# main1.net
KiCad netlist of a schematic drawn in EAGLE
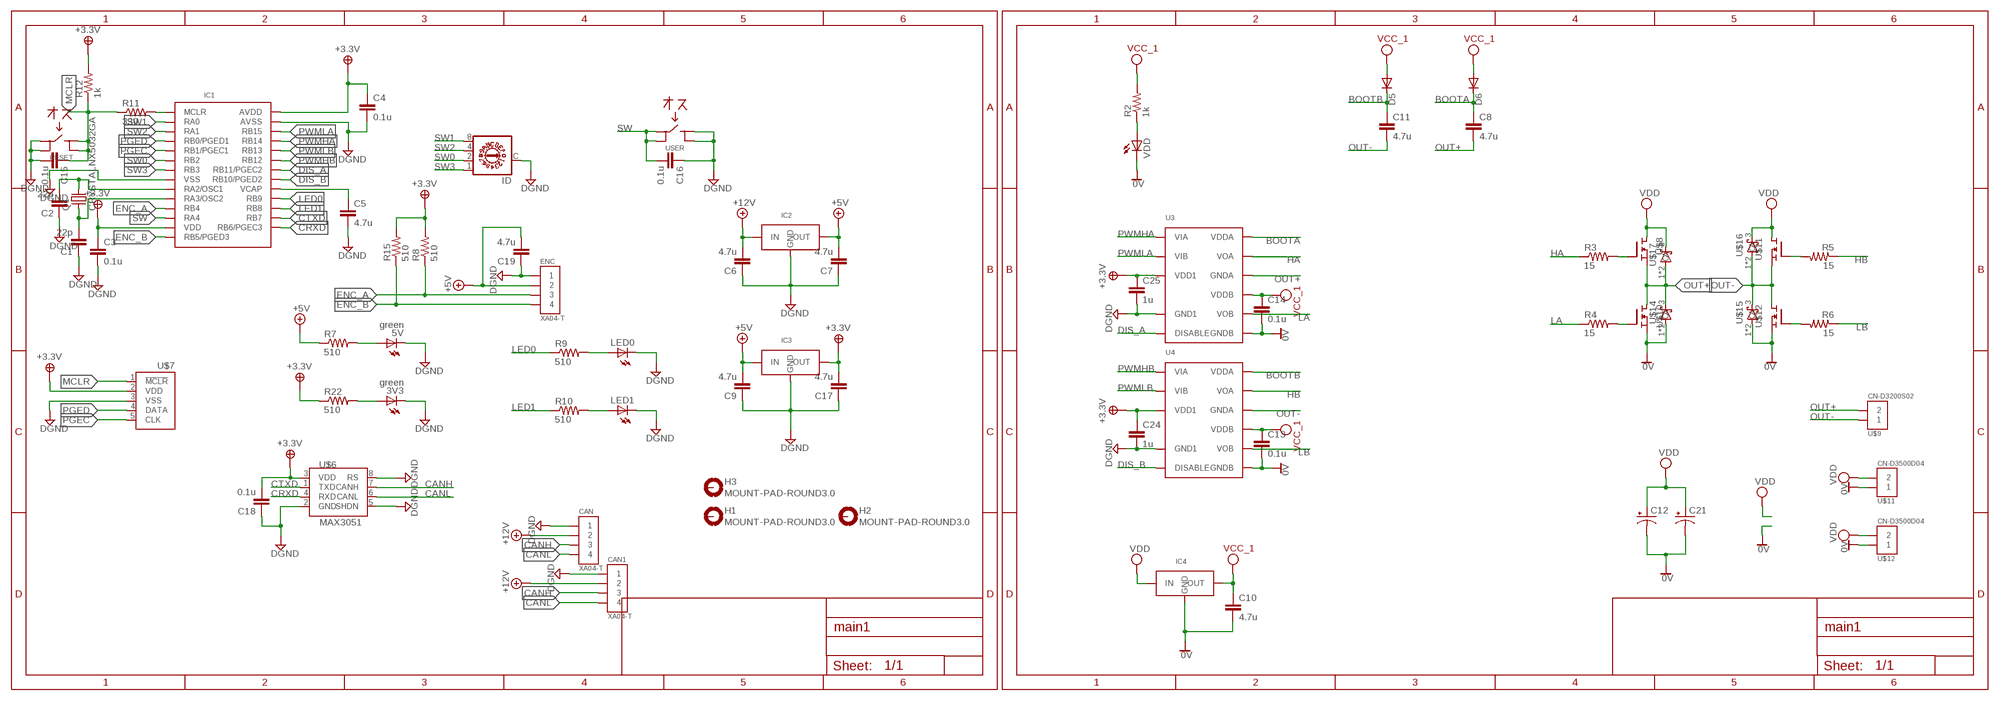
[diagram p0: schematic, sheet 1]

(export (version "E")
  (design (tool "Eeschema 10.0.6"))
  (components
    (comp (ref "3V3")
      (value "green")
      (footprint "eagle-import:CHIPLED_0603")
      (libsource (lib "eagle-import") (part "LEDCHIPLED_0603"))
    )
    (comp (ref "5V")
      (value "green")
      (footprint "eagle-import:CHIPLED_0603")
      (libsource (lib "eagle-import") (part "LEDCHIPLED_0603"))
    )
    (comp (ref "C1")
      (value "22p")
      (footprint "eagle-import:C0603K")
      (libsource (lib "eagle-import") (part "C-EUC0603K"))
    )
    (comp (ref "C2")
      (value "22p")
      (footprint "eagle-import:C0603K")
      (libsource (lib "eagle-import") (part "C-EUC0603K"))
    )
    (comp (ref "C3")
      (value "0.1u")
      (footprint "eagle-import:C0603K")
      (libsource (lib "eagle-import") (part "C-EUC0603K"))
    )
    (comp (ref "C4")
      (value "0.1u")
      (footprint "eagle-import:C0603K")
      (libsource (lib "eagle-import") (part "C-EUC0603K"))
    )
    (comp (ref "C5")
      (value "4.7u")
      (footprint "eagle-import:C0805K")
      (libsource (lib "eagle-import") (part "C-EUC0805K"))
    )
    (comp (ref "C6")
      (value "4.7u")
      (footprint "eagle-import:C0805K")
      (libsource (lib "eagle-import") (part "C-EUC0805K"))
    )
    (comp (ref "C7")
      (value "4.7u")
      (footprint "eagle-import:C0805K")
      (libsource (lib "eagle-import") (part "C-EUC0805K"))
    )
    (comp (ref "C8")
      (value "4.7u")
      (footprint "eagle-import:C0805K")
      (libsource (lib "eagle-import") (part "C-EUC0805K"))
    )
    (comp (ref "C9")
      (value "4.7u")
      (footprint "eagle-import:C0805K")
      (libsource (lib "eagle-import") (part "C-EUC0805K"))
    )
    (comp (ref "C10")
      (value "4.7u")
      (footprint "eagle-import:C0805K")
      (libsource (lib "eagle-import") (part "C-EUC0805K"))
    )
    (comp (ref "C11")
      (value "4.7u")
      (footprint "eagle-import:C0805K")
      (libsource (lib "eagle-import") (part "C-EUC0805K"))
    )
    (comp (ref "C12")
      (value "CPOL-USG")
      (footprint "eagle-import:PANASONIC_G")
      (libsource (lib "eagle-import") (part "CPOL-USG"))
    )
    (comp (ref "C13")
      (value "0.1u")
      (footprint "eagle-import:C0805K")
      (libsource (lib "eagle-import") (part "C-EUC0805K"))
    )
    (comp (ref "C14")
      (value "0.1u")
      (footprint "eagle-import:C0805K")
      (libsource (lib "eagle-import") (part "C-EUC0805K"))
    )
    (comp (ref "C15")
      (value "0.1u")
      (footprint "eagle-import:C0603K")
      (libsource (lib "eagle-import") (part "C-EUC0603K"))
    )
    (comp (ref "C16")
      (value "0.1u")
      (footprint "eagle-import:C0603K")
      (libsource (lib "eagle-import") (part "C-EUC0603K"))
    )
    (comp (ref "C17")
      (value "4.7u")
      (footprint "eagle-import:C0805K")
      (libsource (lib "eagle-import") (part "C-EUC0805K"))
    )
    (comp (ref "C18")
      (value "0.1u")
      (footprint "eagle-import:C0603K")
      (libsource (lib "eagle-import") (part "C-EUC0603K"))
    )
    (comp (ref "C19")
      (value "4.7u")
      (footprint "eagle-import:C0805K")
      (libsource (lib "eagle-import") (part "C-EUC0805K"))
    )
    (comp (ref "C21")
      (value "CPOL-USG")
      (footprint "eagle-import:PANASONIC_G")
      (libsource (lib "eagle-import") (part "CPOL-USG"))
    )
    (comp (ref "C24")
      (value "1u")
      (footprint "eagle-import:C0603K")
      (libsource (lib "eagle-import") (part "C-EUC0603K"))
    )
    (comp (ref "C25")
      (value "1u")
      (footprint "eagle-import:C0603K")
      (libsource (lib "eagle-import") (part "C-EUC0603K"))
    )
    (comp (ref "CAN")
      (value "XA04-T")
      (footprint "eagle-import:XA04")
      (libsource (lib "eagle-import") (part "XA04-T"))
    )
    (comp (ref "CAN1")
      (value "XA04-T")
      (footprint "eagle-import:XA04")
      (libsource (lib "eagle-import") (part "XA04-T"))
    )
    (comp (ref "D5")
      (value "DIODE-SOD123")
      (footprint "eagle-import:SOD123")
      (libsource (lib "eagle-import") (part "DIODE-SOD123"))
    )
    (comp (ref "D6")
      (value "DIODE-SOD123")
      (footprint "eagle-import:SOD123")
      (libsource (lib "eagle-import") (part "DIODE-SOD123"))
    )
    (comp (ref "ENC")
      (value "XA04-T")
      (footprint "eagle-import:XA04")
      (libsource (lib "eagle-import") (part "XA04-T"))
    )
    (comp (ref "H1")
      (value "MOUNT-PAD-ROUND3.0")
      (footprint "eagle-import:3,0-PAD")
      (libsource (lib "eagle-import") (part "MOUNT-PAD-ROUND3.0"))
    )
    (comp (ref "H2")
      (value "MOUNT-PAD-ROUND3.0")
      (footprint "eagle-import:3,0-PAD")
      (libsource (lib "eagle-import") (part "MOUNT-PAD-ROUND3.0"))
    )
    (comp (ref "H3")
      (value "MOUNT-PAD-ROUND3.0")
      (footprint "eagle-import:3,0-PAD")
      (libsource (lib "eagle-import") (part "MOUNT-PAD-ROUND3.0"))
    )
    (comp (ref "IC1")
      (value "DSPIC33FJ128MC802")
      (footprint "eagle-import:SOIC28")
      (libsource (lib "eagle-import") (part "DSPIC33FJ128MC802"))
    )
    (comp (ref "IC2")
      (value "REGULATER_MIC39100-5.0WS")
      (footprint "eagle-import:SOT-223")
      (libsource (lib "eagle-import") (part "REGULATER_MIC39100-3.3WS"))
    )
    (comp (ref "IC3")
      (value "REGULATER_AZ1117CR")
      (footprint "eagle-import:SOT89")
      (libsource (lib "eagle-import") (part "REGULATER_AZ1117CR"))
    )
    (comp (ref "IC4")
      (value "REGULATER_MIC2940A-5.0WU")
      (footprint "eagle-import:TO-263-3")
      (libsource (lib "eagle-import") (part "REGULATER_MIC2940A-5.0WU"))
    )
    (comp (ref "ID")
      (value "A1353HEX")
      (footprint "eagle-import:A1353HEX")
      (libsource (lib "eagle-import") (part "A1353HEX"))
    )
    (comp (ref "LED0")
      (value "LEDCHIPLED_0603")
      (footprint "eagle-import:CHIPLED_0603")
      (libsource (lib "eagle-import") (part "LEDCHIPLED_0603"))
    )
    (comp (ref "LED1")
      (value "LEDCHIPLED_0603")
      (footprint "eagle-import:CHIPLED_0603")
      (libsource (lib "eagle-import") (part "LEDCHIPLED_0603"))
    )
    (comp (ref "Q1")
      (value "CRYSTALNX5032GA")
      (footprint "eagle-import:NX5032GA")
      (libsource (lib "eagle-import") (part "CRYSTALNX5032GA"))
    )
    (comp (ref "R2")
      (value "1k")
      (footprint "eagle-import:R0603")
      (libsource (lib "eagle-import") (part "R-US_R0603"))
    )
    (comp (ref "R3")
      (value "15")
      (footprint "eagle-import:R2512")
      (libsource (lib "eagle-import") (part "R-US_R2512"))
    )
    (comp (ref "R4")
      (value "15")
      (footprint "eagle-import:R2512")
      (libsource (lib "eagle-import") (part "R-US_R2512"))
    )
    (comp (ref "R5")
      (value "15")
      (footprint "eagle-import:R2512")
      (libsource (lib "eagle-import") (part "R-US_R2512"))
    )
    (comp (ref "R6")
      (value "15")
      (footprint "eagle-import:R2512")
      (libsource (lib "eagle-import") (part "R-US_R2512"))
    )
    (comp (ref "R7")
      (value "510")
      (footprint "eagle-import:R0603")
      (libsource (lib "eagle-import") (part "R-US_R0603"))
    )
    (comp (ref "R8")
      (value "510")
      (footprint "eagle-import:R0603")
      (libsource (lib "eagle-import") (part "R-US_R0603"))
    )
    (comp (ref "R9")
      (value "510")
      (footprint "eagle-import:R0603")
      (libsource (lib "eagle-import") (part "R-US_R0603"))
    )
    (comp (ref "R10")
      (value "510")
      (footprint "eagle-import:R0603")
      (libsource (lib "eagle-import") (part "R-US_R0603"))
    )
    (comp (ref "R11")
      (value "330")
      (footprint "eagle-import:R0603")
      (libsource (lib "eagle-import") (part "R-US_R0603"))
    )
    (comp (ref "R12")
      (value "1k")
      (footprint "eagle-import:R0603")
      (libsource (lib "eagle-import") (part "R-US_R0603"))
    )
    (comp (ref "R15")
      (value "510")
      (footprint "eagle-import:R0603")
      (libsource (lib "eagle-import") (part "R-US_R0603"))
    )
    (comp (ref "R22")
      (value "510")
      (footprint "eagle-import:R0603")
      (libsource (lib "eagle-import") (part "R-US_R0603"))
    )
    (comp (ref "RESET")
      (value "SWITCH_4PALPS")
      (footprint "eagle-import:SKRP")
      (libsource (lib "eagle-import") (part "SWITCH_4PALPS"))
    )
    (comp (ref "U$1")
      (value "CN-D3500D04")
      (footprint "eagle-import:D-3500D04")
      (libsource (lib "eagle-import") (part "CN-D3500D04"))
    )
    (comp (ref "U$6")
      (value "MAX3051")
      (footprint "eagle-import:SOIC8")
      (libsource (lib "eagle-import") (part "MAX3051"))
    )
    (comp (ref "U$7")
      (value "WRITE_FOR_PICT")
      (footprint "eagle-import:ZH05")
      (libsource (lib "eagle-import") (part "WRITE_FOR_PICT"))
    )
    (comp (ref "U$8")
      (value "FET_NCH_FMDS86500L")
      (footprint "eagle-import:PQFN_5X6_8L(POWER_56)")
      (libsource (lib "eagle-import") (part "FET_NCH_FMDS86500L"))
    )
    (comp (ref "U$9")
      (value "CN-D3200S02")
      (footprint "eagle-import:D-3200S02-S")
      (libsource (lib "eagle-import") (part "CN-D3200S02"))
    )
    (comp (ref "U$10")
      (value "FET_NCH_FMDS86500L")
      (footprint "eagle-import:PQFN_5X6_8L(POWER_56)")
      (libsource (lib "eagle-import") (part "FET_NCH_FMDS86500L"))
    )
    (comp (ref "U$11")
      (value "FET_NCH_FMDS86500L")
      (footprint "eagle-import:PQFN_5X6_8L(POWER_56)")
      (libsource (lib "eagle-import") (part "FET_NCH_FMDS86500L"))
    )
    (comp (ref "U$12")
      (value "FET_NCH_FMDS86500L")
      (footprint "eagle-import:PQFN_5X6_8L(POWER_56)")
      (libsource (lib "eagle-import") (part "FET_NCH_FMDS86500L"))
    )
    (comp (ref "U$14")
      (value "SCHOTTKY_BARRIER_DIODE_FSV560")
      (footprint "eagle-import:TO-277")
      (libsource (lib "eagle-import") (part "SCHOTTKY_BARRIER_DIODE_FSV560"))
    )
    (comp (ref "U$15")
      (value "SCHOTTKY_BARRIER_DIODE_FSV560")
      (footprint "eagle-import:TO-277")
      (libsource (lib "eagle-import") (part "SCHOTTKY_BARRIER_DIODE_FSV560"))
    )
    (comp (ref "U$16")
      (value "SCHOTTKY_BARRIER_DIODE_FSV560")
      (footprint "eagle-import:TO-277")
      (libsource (lib "eagle-import") (part "SCHOTTKY_BARRIER_DIODE_FSV560"))
    )
    (comp (ref "U$17")
      (value "SCHOTTKY_BARRIER_DIODE_FSV560")
      (footprint "eagle-import:TO-277")
      (libsource (lib "eagle-import") (part "SCHOTTKY_BARRIER_DIODE_FSV560"))
    )
    (comp (ref "U3")
      (value "ADUM3223_SMD")
      (footprint "eagle-import:SOIC16_N")
      (libsource (lib "eagle-import") (part "ADUM3223_SMD"))
    )
    (comp (ref "U4")
      (value "ADUM3223_SMD")
      (footprint "eagle-import:SOIC16_N")
      (libsource (lib "eagle-import") (part "ADUM3223_SMD"))
    )
    (comp (ref "USER")
      (value "SWITCH_4PALPS")
      (footprint "eagle-import:SKRP")
      (libsource (lib "eagle-import") (part "SWITCH_4PALPS"))
    )
    (comp (ref "VDD")
      (value "LEDCHIPLED_0603")
      (footprint "eagle-import:CHIPLED_0603")
      (libsource (lib "eagle-import") (part "LEDCHIPLED_0603"))
    )
  )
  (nets
    (net (code "1") (name "+3.3V") (class "Default")
      (node (ref "C17") (pin "2") (pinfunction "2_2") (pintype "passive"))
      (node (ref "C18") (pin "2") (pinfunction "2_2") (pintype "passive"))
      (node (ref "C24") (pin "1") (pinfunction "1_1") (pintype "passive"))
      (node (ref "C25") (pin "1") (pinfunction "1_1") (pintype "passive"))
      (node (ref "C3") (pin "1") (pinfunction "1_1") (pintype "passive"))
      (node (ref "C4") (pin "1") (pinfunction "1_1") (pintype "passive"))
      (node (ref "IC1") (pin "13") (pinfunction "VDD_13") (pintype "bidirectional"))
      (node (ref "IC1") (pin "28") (pinfunction "AVDD_28") (pintype "bidirectional"))
      (node (ref "IC3") (pin "2") (pinfunction "OUT_2") (pintype "bidirectional"))
      (node (ref "IC3") (pin "P") (pinfunction "OUT_P") (pintype "bidirectional"))
      (node (ref "R12") (pin "2") (pinfunction "2_2") (pintype "passive"))
      (node (ref "R15") (pin "2") (pinfunction "2_2") (pintype "passive"))
      (node (ref "R22") (pin "1") (pinfunction "1_1") (pintype "passive"))
      (node (ref "R8") (pin "2") (pinfunction "2_2") (pintype "passive"))
      (node (ref "U$6") (pin "3") (pinfunction "VDD_3") (pintype "bidirectional"))
      (node (ref "U$7") (pin "2") (pinfunction "VDD_2") (pintype "bidirectional"))
      (node (ref "U3") (pin "P$3") (pinfunction "VDD1_P$3") (pintype "bidirectional"))
      (node (ref "U3") (pin "P$8") (pinfunction "VDD1_P$8") (pintype "bidirectional"))
      (node (ref "U4") (pin "P$3") (pinfunction "VDD1_P$3") (pintype "bidirectional"))
      (node (ref "U4") (pin "P$8") (pinfunction "VDD1_P$8") (pintype "bidirectional"))
    )
    (net (code "2") (name "+5V") (class "Default")
      (node (ref "C19") (pin "2") (pinfunction "2_2") (pintype "passive"))
      (node (ref "C7") (pin "2") (pinfunction "2_2") (pintype "passive"))
      (node (ref "C9") (pin "2") (pinfunction "2_2") (pintype "passive"))
      (node (ref "ENC") (pin "PIN2") (pinfunction "2_PIN2") (pintype "bidirectional"))
      (node (ref "IC2") (pin "3") (pinfunction "OUT_3") (pintype "bidirectional"))
      (node (ref "IC3") (pin "3") (pinfunction "IN_3") (pintype "bidirectional"))
      (node (ref "R7") (pin "1") (pinfunction "1_1") (pintype "passive"))
    )
    (net (code "3") (name "+12V") (class "Default")
      (node (ref "C6") (pin "2") (pinfunction "2_2") (pintype "passive"))
      (node (ref "CAN") (pin "PIN2") (pinfunction "2_PIN2") (pintype "bidirectional"))
      (node (ref "CAN1") (pin "PIN2") (pinfunction "2_PIN2") (pintype "bidirectional"))
      (node (ref "IC2") (pin "1") (pinfunction "IN_1") (pintype "bidirectional"))
    )
    (net (code "4") (name "/BOOTA") (class "Default")
      (node (ref "C8") (pin "1") (pinfunction "1_1") (pintype "passive"))
      (node (ref "D6") (pin "C") (pinfunction "C_C") (pintype "passive"))
      (node (ref "U3") (pin "P$16") (pinfunction "VDDA_P$16") (pintype "bidirectional"))
    )
    (net (code "5") (name "/BOOTB") (class "Default")
      (node (ref "C11") (pin "1") (pinfunction "1_1") (pintype "passive"))
      (node (ref "D5") (pin "C") (pinfunction "C_C") (pintype "passive"))
      (node (ref "U4") (pin "P$16") (pinfunction "VDDA_P$16") (pintype "bidirectional"))
    )
    (net (code "6") (name "/HA") (class "Default")
      (node (ref "R3") (pin "1") (pinfunction "1_1") (pintype "passive"))
      (node (ref "U3") (pin "P$15") (pinfunction "VOA_P$15") (pintype "bidirectional"))
    )
    (net (code "7") (name "/HB") (class "Default")
      (node (ref "R5") (pin "1") (pinfunction "1_1") (pintype "passive"))
      (node (ref "U4") (pin "P$15") (pinfunction "VOA_P$15") (pintype "bidirectional"))
    )
    (net (code "8") (name "/LA") (class "Default")
      (node (ref "R4") (pin "1") (pinfunction "1_1") (pintype "passive"))
      (node (ref "U3") (pin "P$10") (pinfunction "VOB_P$10") (pintype "bidirectional"))
    )
    (net (code "9") (name "/LB") (class "Default")
      (node (ref "R6") (pin "1") (pinfunction "1_1") (pintype "passive"))
      (node (ref "U4") (pin "P$10") (pinfunction "VOB_P$10") (pintype "bidirectional"))
    )
    (net (code "10") (name "0V") (class "Default")
      (node (ref "C10") (pin "2") (pinfunction "2_2") (pintype "passive"))
      (node (ref "C12") (pin "-") (pinfunction "-_-") (pintype "passive"))
      (node (ref "C13") (pin "2") (pinfunction "2_2") (pintype "passive"))
      (node (ref "C14") (pin "2") (pinfunction "2_2") (pintype "passive"))
      (node (ref "C21") (pin "-") (pinfunction "-_-") (pintype "passive"))
      (node (ref "IC4") (pin "2") (pinfunction "GND_2") (pintype "bidirectional"))
      (node (ref "IC4") (pin "PAD") (pinfunction "GND_PAD") (pintype "bidirectional"))
      (node (ref "U$1") (pin "01A") (pinfunction "1_01A") (pintype "bidirectional"))
      (node (ref "U$1") (pin "02A") (pinfunction "1_02A") (pintype "bidirectional"))
      (node (ref "U$10") (pin "1") (pinfunction "S_1") (pintype "bidirectional"))
      (node (ref "U$10") (pin "2") (pinfunction "S_2") (pintype "bidirectional"))
      (node (ref "U$10") (pin "3") (pinfunction "S_3") (pintype "bidirectional"))
      (node (ref "U$12") (pin "1") (pinfunction "S_1") (pintype "bidirectional"))
      (node (ref "U$12") (pin "2") (pinfunction "S_2") (pintype "bidirectional"))
      (node (ref "U$12") (pin "3") (pinfunction "S_3") (pintype "bidirectional"))
      (node (ref "U$14") (pin "1") (pinfunction "A_1") (pintype "bidirectional"))
      (node (ref "U$14") (pin "2") (pinfunction "A_2") (pintype "bidirectional"))
      (node (ref "U$15") (pin "1") (pinfunction "A_1") (pintype "bidirectional"))
      (node (ref "U$15") (pin "2") (pinfunction "A_2") (pintype "bidirectional"))
      (node (ref "U3") (pin "P$9") (pinfunction "GNDB_P$9") (pintype "bidirectional"))
      (node (ref "U4") (pin "P$9") (pinfunction "GNDB_P$9") (pintype "bidirectional"))
      (node (ref "VDD") (pin "C") (pinfunction "C_C") (pintype "passive"))
    )
    (net (code "11") (name "CANH") (class "Default")
      (node (ref "CAN") (pin "PIN3") (pinfunction "3_PIN3") (pintype "bidirectional"))
      (node (ref "CAN1") (pin "PIN3") (pinfunction "3_PIN3") (pintype "bidirectional"))
      (node (ref "U$6") (pin "7") (pinfunction "CANH_7") (pintype "bidirectional"))
    )
    (net (code "12") (name "CANL") (class "Default")
      (node (ref "CAN") (pin "PIN4") (pinfunction "4_PIN4") (pintype "bidirectional"))
      (node (ref "CAN1") (pin "PIN4") (pinfunction "4_PIN4") (pintype "bidirectional"))
      (node (ref "U$6") (pin "6") (pinfunction "CANL_6") (pintype "bidirectional"))
    )
    (net (code "13") (name "CRXD") (class "Default")
      (node (ref "IC1") (pin "15") (pinfunction "RB6/PGEC3_15") (pintype "bidirectional"))
      (node (ref "U$6") (pin "4") (pinfunction "RXD_4") (pintype "bidirectional"))
    )
    (net (code "14") (name "CTXD") (class "Default")
      (node (ref "IC1") (pin "16") (pinfunction "RB7_16") (pintype "bidirectional"))
      (node (ref "U$6") (pin "1") (pinfunction "TXD_1") (pintype "bidirectional"))
    )
    (net (code "15") (name "DGND") (class "Default")
      (node (ref "3V3") (pin "C") (pinfunction "C_C") (pintype "passive"))
      (node (ref "5V") (pin "C") (pinfunction "C_C") (pintype "passive"))
      (node (ref "C1") (pin "1") (pinfunction "1_1") (pintype "passive"))
      (node (ref "C15") (pin "2") (pinfunction "2_2") (pintype "passive"))
      (node (ref "C16") (pin "1") (pinfunction "1_1") (pintype "passive"))
      (node (ref "C17") (pin "1") (pinfunction "1_1") (pintype "passive"))
      (node (ref "C18") (pin "1") (pinfunction "1_1") (pintype "passive"))
      (node (ref "C19") (pin "1") (pinfunction "1_1") (pintype "passive"))
      (node (ref "C2") (pin "1") (pinfunction "1_1") (pintype "passive"))
      (node (ref "C24") (pin "2") (pinfunction "2_2") (pintype "passive"))
      (node (ref "C25") (pin "2") (pinfunction "2_2") (pintype "passive"))
      (node (ref "C3") (pin "2") (pinfunction "2_2") (pintype "passive"))
      (node (ref "C4") (pin "2") (pinfunction "2_2") (pintype "passive"))
      (node (ref "C5") (pin "2") (pinfunction "2_2") (pintype "passive"))
      (node (ref "C6") (pin "1") (pinfunction "1_1") (pintype "passive"))
      (node (ref "C7") (pin "1") (pinfunction "1_1") (pintype "passive"))
      (node (ref "C9") (pin "1") (pinfunction "1_1") (pintype "passive"))
      (node (ref "CAN") (pin "PIN1") (pinfunction "1_PIN1") (pintype "bidirectional"))
      (node (ref "CAN1") (pin "PIN1") (pinfunction "1_PIN1") (pintype "bidirectional"))
      (node (ref "ENC") (pin "PIN1") (pinfunction "1_PIN1") (pintype "bidirectional"))
      (node (ref "IC1") (pin "19") (pinfunction "VSS_19") (pintype "bidirectional"))
      (node (ref "IC1") (pin "27") (pinfunction "AVSS_27") (pintype "bidirectional"))
      (node (ref "IC1") (pin "8") (pinfunction "VSS_8") (pintype "bidirectional"))
      (node (ref "IC2") (pin "2") (pinfunction "GND_2") (pintype "bidirectional"))
      (node (ref "IC2") (pin "TAB") (pinfunction "GND_TAB") (pintype "bidirectional"))
      (node (ref "IC3") (pin "1") (pinfunction "GND_1") (pintype "bidirectional"))
      (node (ref "ID") (pin "C") (pinfunction "C_C") (pintype "passive"))
      (node (ref "LED0") (pin "C") (pinfunction "C_C") (pintype "passive"))
      (node (ref "LED1") (pin "C") (pinfunction "C_C") (pintype "passive"))
      (node (ref "RESET") (pin "1") (pinfunction "1_1") (pintype "bidirectional"))
      (node (ref "RESET") (pin "2") (pinfunction "2_2") (pintype "bidirectional"))
      (node (ref "U$6") (pin "2") (pinfunction "GND_2") (pintype "bidirectional"))
      (node (ref "U$6") (pin "5") (pinfunction "SHDN_5") (pintype "bidirectional"))
      (node (ref "U$6") (pin "8") (pinfunction "RS_8") (pintype "bidirectional"))
      (node (ref "U$7") (pin "3") (pinfunction "VSS_3") (pintype "bidirectional"))
      (node (ref "U3") (pin "P$4") (pinfunction "GND1_P$4") (pintype "bidirectional"))
      (node (ref "U4") (pin "P$4") (pinfunction "GND1_P$4") (pintype "bidirectional"))
      (node (ref "USER") (pin "3") (pinfunction "3_3") (pintype "bidirectional"))
      (node (ref "USER") (pin "4") (pinfunction "4_4") (pintype "bidirectional"))
    )
    (net (code "16") (name "DIS_A") (class "Default")
      (node (ref "IC1") (pin "22") (pinfunction "RB11/PGEC2_22") (pintype "bidirectional"))
      (node (ref "U3") (pin "P$5") (pinfunction "DISABLE_P$5") (pintype "bidirectional"))
    )
    (net (code "17") (name "DIS_B") (class "Default")
      (node (ref "IC1") (pin "21") (pinfunction "RB10/PGED2_21") (pintype "bidirectional"))
      (node (ref "U4") (pin "P$5") (pinfunction "DISABLE_P$5") (pintype "bidirectional"))
    )
    (net (code "18") (name "ENC_A") (class "Default")
      (node (ref "ENC") (pin "PIN3") (pinfunction "3_PIN3") (pintype "bidirectional"))
      (node (ref "IC1") (pin "11") (pinfunction "RB4_11") (pintype "bidirectional"))
      (node (ref "R8") (pin "1") (pinfunction "1_1") (pintype "passive"))
    )
    (net (code "19") (name "ENC_B") (class "Default")
      (node (ref "ENC") (pin "PIN4") (pinfunction "4_PIN4") (pintype "bidirectional"))
      (node (ref "IC1") (pin "14") (pinfunction "RB5/PGED3_14") (pintype "bidirectional"))
      (node (ref "R15") (pin "1") (pinfunction "1_1") (pintype "passive"))
    )
    (net (code "20") (name "LED0") (class "Default")
      (node (ref "IC1") (pin "18") (pinfunction "RB9_18") (pintype "bidirectional"))
      (node (ref "R9") (pin "1") (pinfunction "1_1") (pintype "passive"))
    )
    (net (code "21") (name "LED1") (class "Default")
      (node (ref "IC1") (pin "17") (pinfunction "RB8_17") (pintype "bidirectional"))
      (node (ref "R10") (pin "1") (pinfunction "1_1") (pintype "passive"))
    )
    (net (code "22") (name "MCLR") (class "Default")
      (node (ref "C15") (pin "1") (pinfunction "1_1") (pintype "passive"))
      (node (ref "R11") (pin "1") (pinfunction "1_1") (pintype "passive"))
      (node (ref "R12") (pin "1") (pinfunction "1_1") (pintype "passive"))
      (node (ref "RESET") (pin "3") (pinfunction "3_3") (pintype "bidirectional"))
      (node (ref "RESET") (pin "4") (pinfunction "4_4") (pintype "bidirectional"))
      (node (ref "U$7") (pin "1") (pinfunction "~{MCLR}_1") (pintype "bidirectional"))
    )
    (net (code "23") (name "Net-(3V3-PadA)") (class "Default")
      (node (ref "3V3") (pin "A") (pinfunction "A_A") (pintype "passive"))
      (node (ref "R22") (pin "2") (pinfunction "2_2") (pintype "passive"))
    )
    (net (code "24") (name "Net-(5V-PadA)") (class "Default")
      (node (ref "5V") (pin "A") (pinfunction "A_A") (pintype "passive"))
      (node (ref "R7") (pin "2") (pinfunction "2_2") (pintype "passive"))
    )
    (net (code "25") (name "Net-(IC1-MCLR)") (class "Default")
      (node (ref "IC1") (pin "1") (pinfunction "MCLR_1") (pintype "bidirectional"))
      (node (ref "R11") (pin "2") (pinfunction "2_2") (pintype "passive"))
    )
    (net (code "26") (name "Net-(IC1-RA2{slash}OSC1)") (class "Default")
      (node (ref "C2") (pin "2") (pinfunction "2_2") (pintype "passive"))
      (node (ref "IC1") (pin "9") (pinfunction "RA2/OSC1_9") (pintype "bidirectional"))
      (node (ref "Q1") (pin "2") (pinfunction "2_2") (pintype "bidirectional"))
    )
    (net (code "27") (name "Net-(IC1-RA3{slash}OSC2)") (class "Default")
      (node (ref "C1") (pin "2") (pinfunction "2_2") (pintype "passive"))
      (node (ref "IC1") (pin "10") (pinfunction "RA3/OSC2_10") (pintype "bidirectional"))
      (node (ref "Q1") (pin "1") (pinfunction "1_1") (pintype "bidirectional"))
    )
    (net (code "28") (name "Net-(IC1-VCAP)") (class "Default")
      (node (ref "C5") (pin "1") (pinfunction "1_1") (pintype "passive"))
      (node (ref "IC1") (pin "20") (pinfunction "VCAP_20") (pintype "bidirectional"))
    )
    (net (code "29") (name "Net-(LED0-PadA)") (class "Default")
      (node (ref "LED0") (pin "A") (pinfunction "A_A") (pintype "passive"))
      (node (ref "R9") (pin "2") (pinfunction "2_2") (pintype "passive"))
    )
    (net (code "30") (name "Net-(LED1-PadA)") (class "Default")
      (node (ref "LED1") (pin "A") (pinfunction "A_A") (pintype "passive"))
      (node (ref "R10") (pin "2") (pinfunction "2_2") (pintype "passive"))
    )
    (net (code "31") (name "Net-(R2-Pad1)") (class "Default")
      (node (ref "R2") (pin "1") (pinfunction "1_1") (pintype "passive"))
      (node (ref "VDD") (pin "A") (pinfunction "A_A") (pintype "passive"))
    )
    (net (code "32") (name "Net-(U$8-G)") (class "Default")
      (node (ref "R3") (pin "2") (pinfunction "2_2") (pintype "passive"))
      (node (ref "U$8") (pin "4") (pinfunction "G_4") (pintype "bidirectional"))
    )
    (net (code "33") (name "Net-(U$10-G)") (class "Default")
      (node (ref "R4") (pin "2") (pinfunction "2_2") (pintype "passive"))
      (node (ref "U$10") (pin "4") (pinfunction "G_4") (pintype "bidirectional"))
    )
    (net (code "34") (name "Net-(U$11-G)") (class "Default")
      (node (ref "R5") (pin "2") (pinfunction "2_2") (pintype "passive"))
      (node (ref "U$11") (pin "4") (pinfunction "G_4") (pintype "bidirectional"))
    )
    (net (code "35") (name "Net-(U$12-G)") (class "Default")
      (node (ref "R6") (pin "2") (pinfunction "2_2") (pintype "passive"))
      (node (ref "U$12") (pin "4") (pinfunction "G_4") (pintype "bidirectional"))
    )
    (net (code "36") (name "OUT+") (class "Default")
      (node (ref "C8") (pin "2") (pinfunction "2_2") (pintype "passive"))
      (node (ref "U$10") (pin "5") (pinfunction "D_5") (pintype "bidirectional"))
      (node (ref "U$10") (pin "6") (pinfunction "D_6") (pintype "bidirectional"))
      (node (ref "U$10") (pin "7") (pinfunction "D_7") (pintype "bidirectional"))
      (node (ref "U$10") (pin "8") (pinfunction "D_8") (pintype "bidirectional"))
      (node (ref "U$10") (pin "PAD") (pinfunction "D_PAD") (pintype "bidirectional"))
      (node (ref "U$14") (pin "3") (pinfunction "C_3") (pintype "bidirectional"))
      (node (ref "U$17") (pin "1") (pinfunction "A_1") (pintype "bidirectional"))
      (node (ref "U$17") (pin "2") (pinfunction "A_2") (pintype "bidirectional"))
      (node (ref "U$8") (pin "1") (pinfunction "S_1") (pintype "bidirectional"))
      (node (ref "U$8") (pin "2") (pinfunction "S_2") (pintype "bidirectional"))
      (node (ref "U$8") (pin "3") (pinfunction "S_3") (pintype "bidirectional"))
      (node (ref "U$9") (pin "2") (pinfunction "2_2") (pintype "bidirectional"))
      (node (ref "U$9") (pin "P$2") (pinfunction "2_P$2") (pintype "bidirectional"))
      (node (ref "U3") (pin "P$14") (pinfunction "GNDA_P$14") (pintype "bidirectional"))
    )
    (net (code "37") (name "OUT-") (class "Default")
      (node (ref "C11") (pin "2") (pinfunction "2_2") (pintype "passive"))
      (node (ref "U$11") (pin "1") (pinfunction "S_1") (pintype "bidirectional"))
      (node (ref "U$11") (pin "2") (pinfunction "S_2") (pintype "bidirectional"))
      (node (ref "U$11") (pin "3") (pinfunction "S_3") (pintype "bidirectional"))
      (node (ref "U$12") (pin "5") (pinfunction "D_5") (pintype "bidirectional"))
      (node (ref "U$12") (pin "6") (pinfunction "D_6") (pintype "bidirectional"))
      (node (ref "U$12") (pin "7") (pinfunction "D_7") (pintype "bidirectional"))
      (node (ref "U$12") (pin "8") (pinfunction "D_8") (pintype "bidirectional"))
      (node (ref "U$12") (pin "PAD") (pinfunction "D_PAD") (pintype "bidirectional"))
      (node (ref "U$15") (pin "3") (pinfunction "C_3") (pintype "bidirectional"))
      (node (ref "U$16") (pin "1") (pinfunction "A_1") (pintype "bidirectional"))
      (node (ref "U$16") (pin "2") (pinfunction "A_2") (pintype "bidirectional"))
      (node (ref "U$9") (pin "1") (pinfunction "1_1") (pintype "bidirectional"))
      (node (ref "U$9") (pin "P$1") (pinfunction "1_P$1") (pintype "bidirectional"))
      (node (ref "U4") (pin "P$14") (pinfunction "GNDA_P$14") (pintype "bidirectional"))
    )
    (net (code "38") (name "PGEC") (class "Default")
      (node (ref "IC1") (pin "5") (pinfunction "RB1/PGEC1_5") (pintype "bidirectional"))
      (node (ref "U$7") (pin "5") (pinfunction "CLK_5") (pintype "bidirectional"))
    )
    (net (code "39") (name "PGED") (class "Default")
      (node (ref "IC1") (pin "4") (pinfunction "RB0/PGED1_4") (pintype "bidirectional"))
      (node (ref "U$7") (pin "4") (pinfunction "DATA_4") (pintype "bidirectional"))
    )
    (net (code "40") (name "PWMHA") (class "Default")
      (node (ref "IC1") (pin "25") (pinfunction "RB14_25") (pintype "bidirectional"))
      (node (ref "U3") (pin "P$1") (pinfunction "VIA_P$1") (pintype "bidirectional"))
    )
    (net (code "41") (name "PWMHB") (class "Default")
      (node (ref "IC1") (pin "23") (pinfunction "RB12_23") (pintype "bidirectional"))
      (node (ref "U4") (pin "P$1") (pinfunction "VIA_P$1") (pintype "bidirectional"))
    )
    (net (code "42") (name "PWMLA") (class "Default")
      (node (ref "IC1") (pin "26") (pinfunction "RB15_26") (pintype "bidirectional"))
      (node (ref "U3") (pin "P$2") (pinfunction "VIB_P$2") (pintype "bidirectional"))
    )
    (net (code "43") (name "PWMLB") (class "Default")
      (node (ref "IC1") (pin "24") (pinfunction "RB13_24") (pintype "bidirectional"))
      (node (ref "U4") (pin "P$2") (pinfunction "VIB_P$2") (pintype "bidirectional"))
    )
    (net (code "44") (name "SW") (class "Default")
      (node (ref "C16") (pin "2") (pinfunction "2_2") (pintype "passive"))
      (node (ref "IC1") (pin "12") (pinfunction "RA4_12") (pintype "bidirectional"))
      (node (ref "USER") (pin "1") (pinfunction "1_1") (pintype "bidirectional"))
      (node (ref "USER") (pin "2") (pinfunction "2_2") (pintype "bidirectional"))
    )
    (net (code "45") (name "SW0") (class "Default")
      (node (ref "IC1") (pin "6") (pinfunction "RB2_6") (pintype "bidirectional"))
      (node (ref "ID") (pin "2") (pinfunction "2_2") (pintype "passive"))
    )
    (net (code "46") (name "SW1") (class "Default")
      (node (ref "IC1") (pin "2") (pinfunction "RA0_2") (pintype "bidirectional"))
      (node (ref "ID") (pin "8") (pinfunction "8_8") (pintype "passive"))
    )
    (net (code "47") (name "SW2") (class "Default")
      (node (ref "IC1") (pin "3") (pinfunction "RA1_3") (pintype "bidirectional"))
      (node (ref "ID") (pin "4") (pinfunction "4_4") (pintype "passive"))
    )
    (net (code "48") (name "SW3") (class "Default")
      (node (ref "IC1") (pin "7") (pinfunction "RB3_7") (pintype "bidirectional"))
      (node (ref "ID") (pin "1") (pinfunction "1_1") (pintype "passive"))
    )
    (net (code "49") (name "VCC_1") (class "Default")
      (node (ref "C10") (pin "1") (pinfunction "1_1") (pintype "passive"))
      (node (ref "C13") (pin "1") (pinfunction "1_1") (pintype "passive"))
      (node (ref "C14") (pin "1") (pinfunction "1_1") (pintype "passive"))
      (node (ref "D5") (pin "A") (pinfunction "A_A") (pintype "passive"))
      (node (ref "D6") (pin "A") (pinfunction "A_A") (pintype "passive"))
      (node (ref "IC4") (pin "3") (pinfunction "OUT_3") (pintype "bidirectional"))
      (node (ref "R2") (pin "2") (pinfunction "2_2") (pintype "passive"))
      (node (ref "U3") (pin "P$11") (pinfunction "VDDB_P$11") (pintype "bidirectional"))
      (node (ref "U4") (pin "P$11") (pinfunction "VDDB_P$11") (pintype "bidirectional"))
    )
    (net (code "50") (name "VDD") (class "Default")
      (node (ref "C12") (pin "+") (pinfunction "+_+") (pintype "passive"))
      (node (ref "C21") (pin "+") (pinfunction "+_+") (pintype "passive"))
      (node (ref "IC4") (pin "1") (pinfunction "IN_1") (pintype "bidirectional"))
      (node (ref "U$1") (pin "01B") (pinfunction "2_01B") (pintype "bidirectional"))
      (node (ref "U$1") (pin "02B") (pinfunction "2_02B") (pintype "bidirectional"))
      (node (ref "U$11") (pin "5") (pinfunction "D_5") (pintype "bidirectional"))
      (node (ref "U$11") (pin "6") (pinfunction "D_6") (pintype "bidirectional"))
      (node (ref "U$11") (pin "7") (pinfunction "D_7") (pintype "bidirectional"))
      (node (ref "U$11") (pin "8") (pinfunction "D_8") (pintype "bidirectional"))
      (node (ref "U$11") (pin "PAD") (pinfunction "D_PAD") (pintype "bidirectional"))
      (node (ref "U$16") (pin "3") (pinfunction "C_3") (pintype "bidirectional"))
      (node (ref "U$17") (pin "3") (pinfunction "C_3") (pintype "bidirectional"))
      (node (ref "U$8") (pin "5") (pinfunction "D_5") (pintype "bidirectional"))
      (node (ref "U$8") (pin "6") (pinfunction "D_6") (pintype "bidirectional"))
      (node (ref "U$8") (pin "7") (pinfunction "D_7") (pintype "bidirectional"))
      (node (ref "U$8") (pin "8") (pinfunction "D_8") (pintype "bidirectional"))
      (node (ref "U$8") (pin "PAD") (pinfunction "D_PAD") (pintype "bidirectional"))
    )
    (net (code "51") (name "unconnected-(H1-MOUNT-PadB3,0)") (class "Default")
      (node (ref "H1") (pin "B3,0") (pinfunction "MOUNT_B3,0") (pintype "passive"))
    )
    (net (code "52") (name "unconnected-(H2-MOUNT-PadB3,0)") (class "Default")
      (node (ref "H2") (pin "B3,0") (pinfunction "MOUNT_B3,0") (pintype "passive"))
    )
    (net (code "53") (name "unconnected-(H3-MOUNT-PadB3,0)") (class "Default")
      (node (ref "H3") (pin "B3,0") (pinfunction "MOUNT_B3,0") (pintype "passive"))
    )
  )
)
